# Power_driver_AMP.net
KiCad netlist of a schematic drawn in Altium Designer
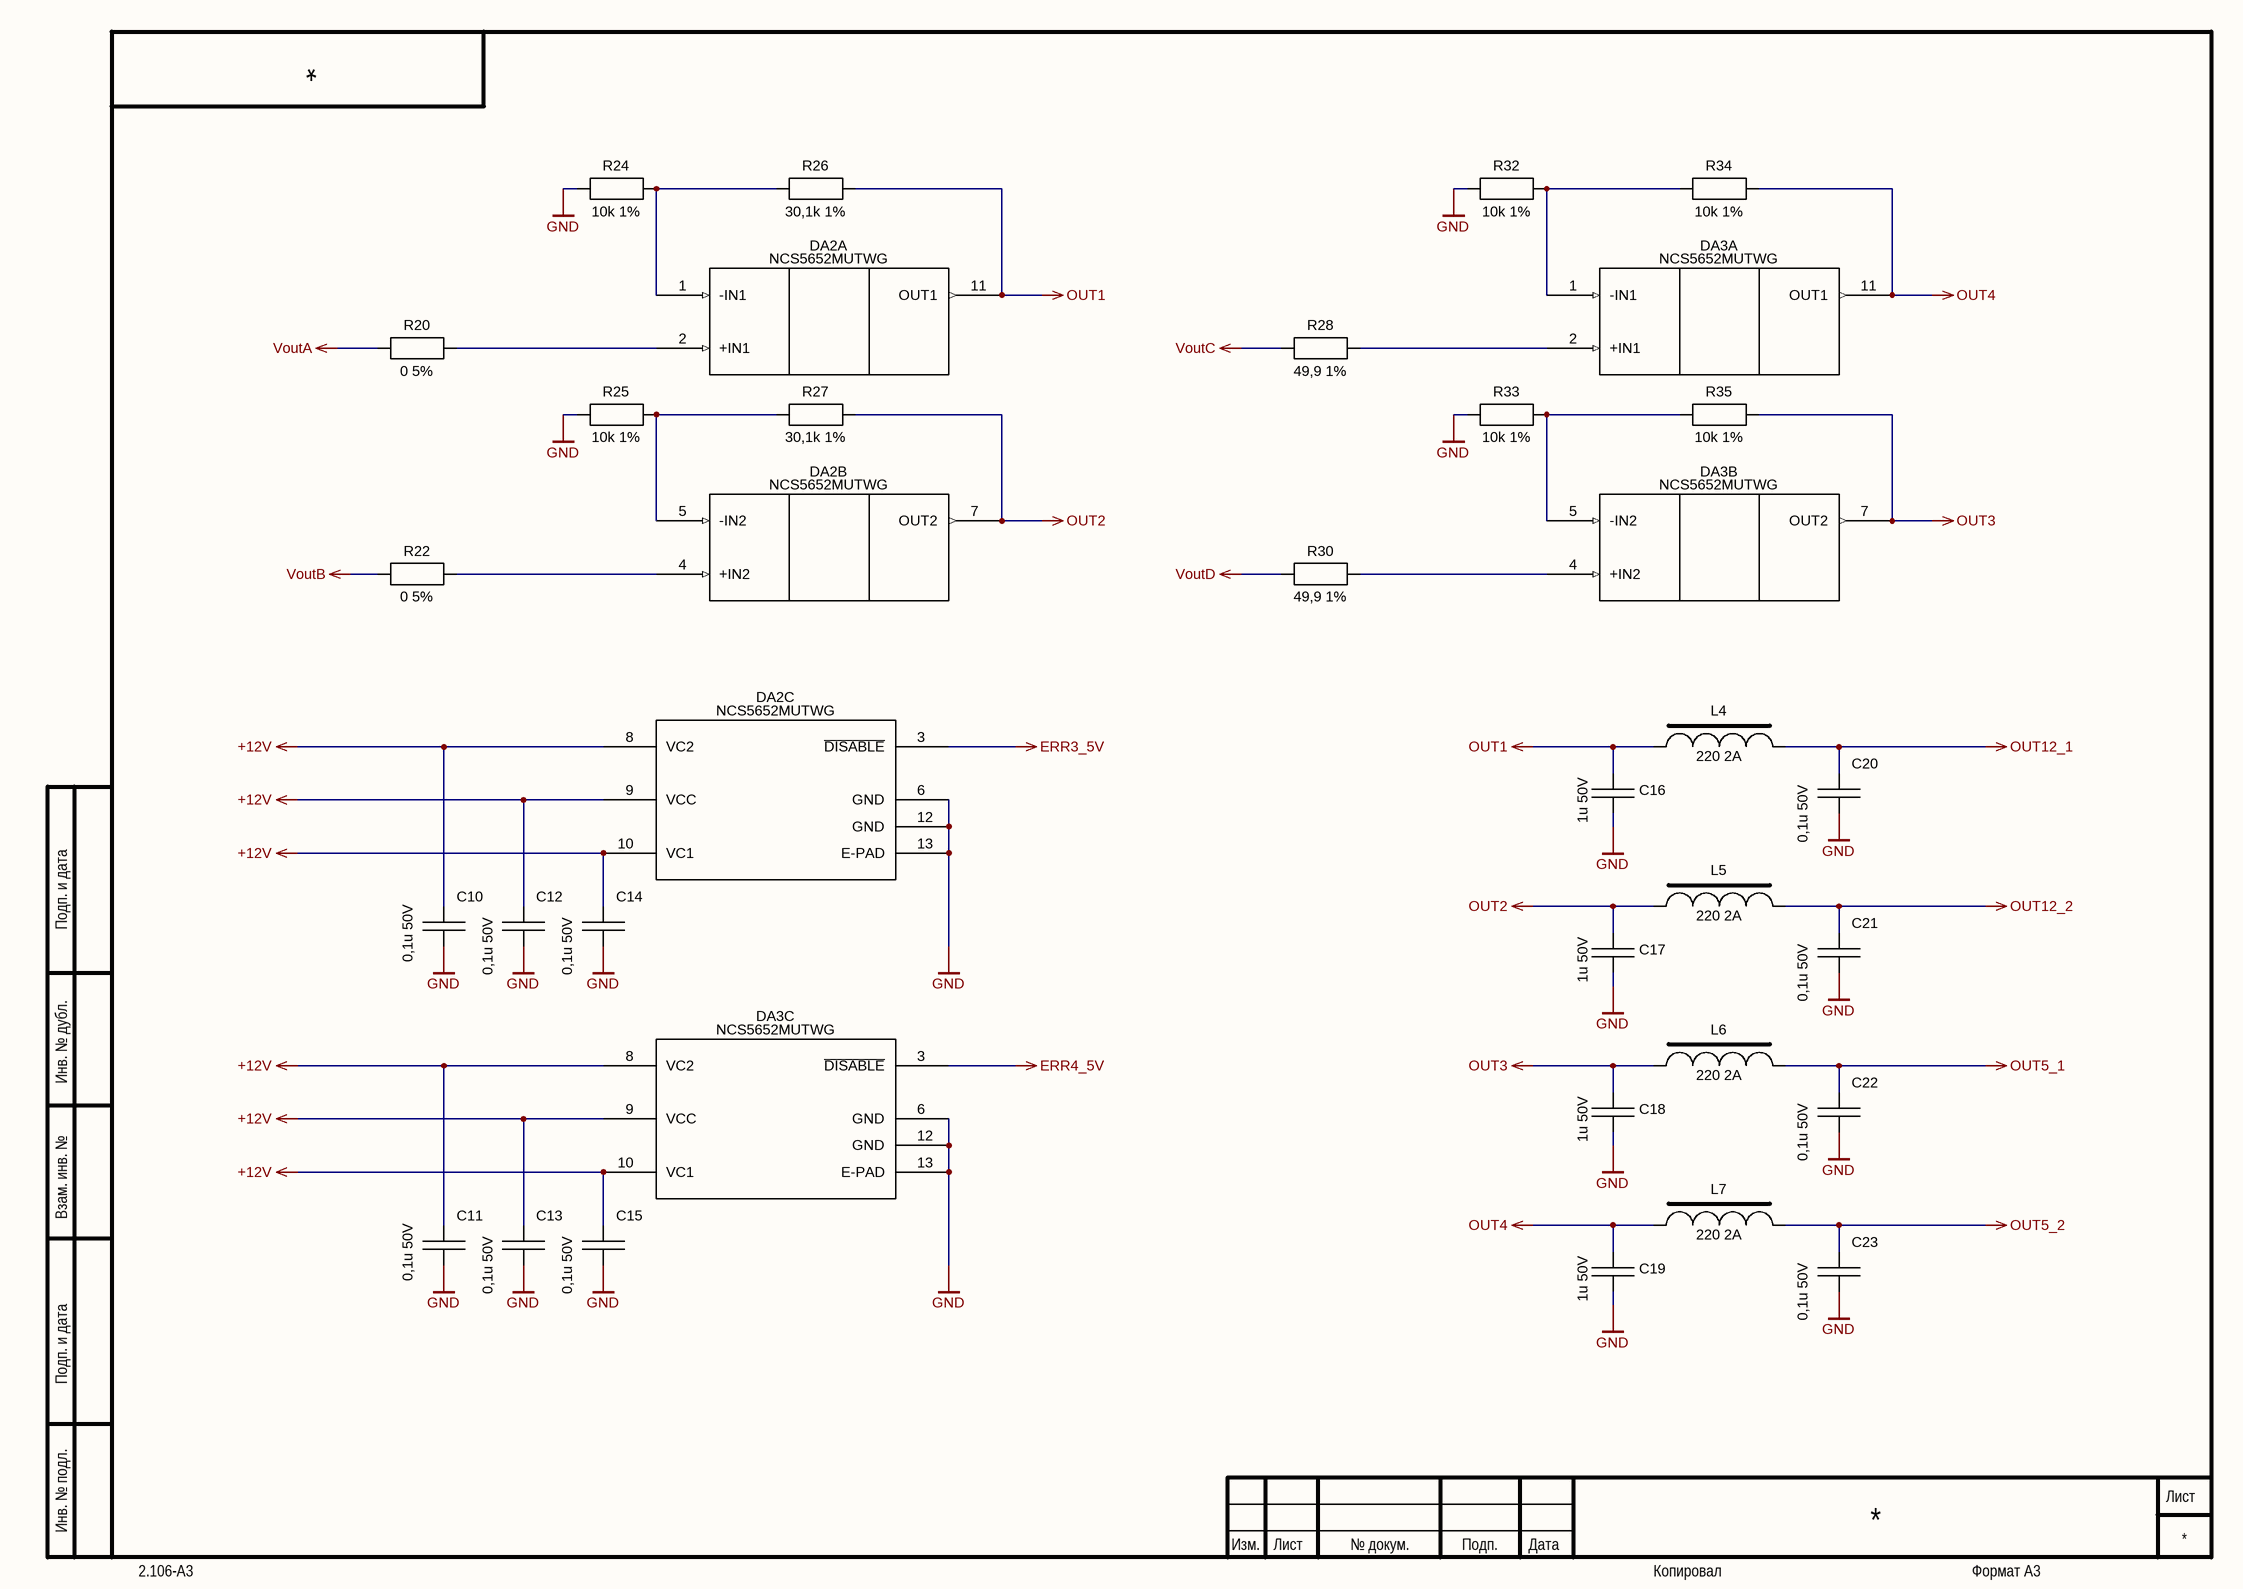
[diagram p0: Power_driver_AMP.SchDoc]

(export (version "E")
  (design (tool "Eeschema 10.0.6"))
  (components
    (comp (ref "C10")
      (value "0,1u 50V")
      (footprint "C0603_CAPC1608X09N")
      (description "Конденсатор керамический (MLCC) общего назначения 0603")
      (fields
        (field (name "PARTNUMBER") "CC0603KRX7R9BB104")
        (field (name "MANUFACTURER") "YAGEO")
        (field (name "DESIGNER") "Dudarev")
      )
      (libsource (lib "RQCLib") (part "Capacitor"))
    )
    (comp (ref "C11")
      (value "0,1u 50V")
      (footprint "C0603_CAPC1608X09N")
      (description "Конденсатор керамический (MLCC) общего назначения 0603")
      (fields
        (field (name "PARTNUMBER") "CC0603KRX7R9BB104")
        (field (name "MANUFACTURER") "YAGEO")
        (field (name "DESIGNER") "Dudarev")
      )
      (libsource (lib "RQCLib") (part "Capacitor"))
    )
    (comp (ref "C12")
      (value "0,1u 50V")
      (footprint "C0603_CAPC1608X09N")
      (description "Конденсатор керамический (MLCC) общего назначения 0603")
      (fields
        (field (name "PARTNUMBER") "CC0603KRX7R9BB104")
        (field (name "MANUFACTURER") "YAGEO")
        (field (name "DESIGNER") "Dudarev")
      )
      (libsource (lib "RQCLib") (part "Capacitor"))
    )
    (comp (ref "C13")
      (value "0,1u 50V")
      (footprint "C0603_CAPC1608X09N")
      (description "Конденсатор керамический (MLCC) общего назначения 0603")
      (fields
        (field (name "PARTNUMBER") "CC0603KRX7R9BB104")
        (field (name "MANUFACTURER") "YAGEO")
        (field (name "DESIGNER") "Dudarev")
      )
      (libsource (lib "RQCLib") (part "Capacitor"))
    )
    (comp (ref "C14")
      (value "0,1u 50V")
      (footprint "C0603_CAPC1608X09N")
      (description "Конденсатор керамический (MLCC) общего назначения 0603")
      (fields
        (field (name "PARTNUMBER") "CC0603KRX7R9BB104")
        (field (name "MANUFACTURER") "YAGEO")
        (field (name "DESIGNER") "Dudarev")
      )
      (libsource (lib "RQCLib") (part "Capacitor"))
    )
    (comp (ref "C15")
      (value "0,1u 50V")
      (footprint "C0603_CAPC1608X09N")
      (description "Конденсатор керамический (MLCC) общего назначения 0603")
      (fields
        (field (name "PARTNUMBER") "CC0603KRX7R9BB104")
        (field (name "MANUFACTURER") "YAGEO")
        (field (name "DESIGNER") "Dudarev")
      )
      (libsource (lib "RQCLib") (part "Capacitor"))
    )
    (comp (ref "C16")
      (value "1u 50V")
      (footprint "C0603_CAPC1608X09N")
      (description "Конденсатор керамический (MLCC) общего назначения 0603")
      (fields
        (field (name "PARTNUMBER") "CC0603KRX7R9BB105")
        (field (name "MANUFACTURER") "YAGEO")
        (field (name "DESIGNER") "Dudarev")
      )
      (libsource (lib "RQCLib") (part "Capacitor"))
    )
    (comp (ref "C17")
      (value "1u 50V")
      (footprint "C0603_CAPC1608X09N")
      (description "Конденсатор керамический (MLCC) общего назначения 0603")
      (fields
        (field (name "PARTNUMBER") "CC0603KRX7R9BB105")
        (field (name "MANUFACTURER") "YAGEO")
        (field (name "DESIGNER") "Dudarev")
      )
      (libsource (lib "RQCLib") (part "Capacitor"))
    )
    (comp (ref "C18")
      (value "1u 50V")
      (footprint "C0603_CAPC1608X09N")
      (description "Конденсатор керамический (MLCC) общего назначения 0603")
      (fields
        (field (name "PARTNUMBER") "CC0603KRX7R9BB105")
        (field (name "MANUFACTURER") "YAGEO")
        (field (name "DESIGNER") "Dudarev")
      )
      (libsource (lib "RQCLib") (part "Capacitor"))
    )
    (comp (ref "C19")
      (value "1u 50V")
      (footprint "C0603_CAPC1608X09N")
      (description "Конденсатор керамический (MLCC) общего назначения 0603")
      (fields
        (field (name "PARTNUMBER") "CC0603KRX7R9BB105")
        (field (name "MANUFACTURER") "YAGEO")
        (field (name "DESIGNER") "Dudarev")
      )
      (libsource (lib "RQCLib") (part "Capacitor"))
    )
    (comp (ref "C20")
      (value "0,1u 50V")
      (footprint "C0603_CAPC1608X09N")
      (description "Конденсатор керамический (MLCC) общего назначения 0603")
      (fields
        (field (name "PARTNUMBER") "CC0603KRX7R9BB104")
        (field (name "MANUFACTURER") "YAGEO")
        (field (name "DESIGNER") "Dudarev")
      )
      (libsource (lib "RQCLib") (part "Capacitor"))
    )
    (comp (ref "C21")
      (value "0,1u 50V")
      (footprint "C0603_CAPC1608X09N")
      (description "Конденсатор керамический (MLCC) общего назначения 0603")
      (fields
        (field (name "PARTNUMBER") "CC0603KRX7R9BB104")
        (field (name "MANUFACTURER") "YAGEO")
        (field (name "DESIGNER") "Dudarev")
      )
      (libsource (lib "RQCLib") (part "Capacitor"))
    )
    (comp (ref "C22")
      (value "0,1u 50V")
      (footprint "C0603_CAPC1608X09N")
      (description "Конденсатор керамический (MLCC) общего назначения 0603")
      (fields
        (field (name "PARTNUMBER") "CC0603KRX7R9BB104")
        (field (name "MANUFACTURER") "YAGEO")
        (field (name "DESIGNER") "Dudarev")
      )
      (libsource (lib "RQCLib") (part "Capacitor"))
    )
    (comp (ref "C23")
      (value "0,1u 50V")
      (footprint "C0603_CAPC1608X09N")
      (description "Конденсатор керамический (MLCC) общего назначения 0603")
      (fields
        (field (name "PARTNUMBER") "CC0603KRX7R9BB104")
        (field (name "MANUFACTURER") "YAGEO")
        (field (name "DESIGNER") "Dudarev")
      )
      (libsource (lib "RQCLib") (part "Capacitor"))
    )
    (comp (ref "DA2")
      (value "NCS5652MUTWG")
      (footprint "UDFN12 3x3, 0.5P")
      (description "High Speed, High Output Current, Dual Operational Amplifier, SMT")
      (libsource (lib "IC_Amplifier") (part "NCS5652MUTWG"))
    )
    (comp (ref "DA3")
      (value "NCS5652MUTWG")
      (footprint "UDFN12 3x3, 0.5P")
      (description "High Speed, High Output Current, Dual Operational Amplifier, SMT")
      (libsource (lib "IC_Amplifier") (part "NCS5652MUTWG"))
    )
    (comp (ref "L4")
      (value "220 2A")
      (footprint "I0805_INDC2012X11N")
      (description "Chip Ferrite Bead 220 Ohm, 2A, 0805")
      (fields
        (field (name "PARTNUMBER") "BLM21PG221SN1D")
        (field (name "MANUFACTURER") "Murata Electronics")
        (field (name "DESIGNER") "Pashinskiy")
      )
      (libsource (lib "RQCLib") (part "Inductor_Core"))
    )
    (comp (ref "L5")
      (value "220 2A")
      (footprint "I0805_INDC2012X11N")
      (description "Chip Ferrite Bead 220 Ohm, 2A, 0805")
      (fields
        (field (name "PARTNUMBER") "BLM21PG221SN1D")
        (field (name "MANUFACTURER") "Murata Electronics")
        (field (name "DESIGNER") "Pashinskiy")
      )
      (libsource (lib "RQCLib") (part "Inductor_Core"))
    )
    (comp (ref "L6")
      (value "220 2A")
      (footprint "I0805_INDC2012X11N")
      (description "Chip Ferrite Bead 220 Ohm, 2A, 0805")
      (fields
        (field (name "PARTNUMBER") "BLM21PG221SN1D")
        (field (name "MANUFACTURER") "Murata Electronics")
        (field (name "DESIGNER") "Pashinskiy")
      )
      (libsource (lib "RQCLib") (part "Inductor_Core"))
    )
    (comp (ref "L7")
      (value "220 2A")
      (footprint "I0805_INDC2012X11N")
      (description "Chip Ferrite Bead 220 Ohm, 2A, 0805")
      (fields
        (field (name "PARTNUMBER") "BLM21PG221SN1D")
        (field (name "MANUFACTURER") "Murata Electronics")
        (field (name "DESIGNER") "Pashinskiy")
      )
      (libsource (lib "RQCLib") (part "Inductor_Core"))
    )
    (comp (ref "R20")
      (value "0 5%")
      (footprint "R0603_RESC1608X06N")
      (description "Резистор толстопленочный общего назначения 0603")
      (fields
        (field (name "PARTNUMBER") "RC0603JR-070RL")
        (field (name "MANUFACTURER") "YAGEO")
        (field (name "DESIGNER") "Dudarev")
      )
      (libsource (lib "RQCLib") (part "Resistor"))
    )
    (comp (ref "R22")
      (value "0 5%")
      (footprint "R0603_RESC1608X06N")
      (description "Резистор толстопленочный общего назначения 0603")
      (fields
        (field (name "PARTNUMBER") "RC0603JR-070RL")
        (field (name "MANUFACTURER") "YAGEO")
        (field (name "DESIGNER") "Dudarev")
      )
      (libsource (lib "RQCLib") (part "Resistor"))
    )
    (comp (ref "R24")
      (value "10k 1%")
      (footprint "R0603_RESC1608X06N")
      (description "Резистор толстопленочный общего назначения 0603")
      (fields
        (field (name "PARTNUMBER") "RC0603FR-0710KL")
        (field (name "MANUFACTURER") "YAGEO")
        (field (name "DESIGNER") "Dudarev")
      )
      (libsource (lib "RQCLib") (part "Resistor"))
    )
    (comp (ref "R25")
      (value "10k 1%")
      (footprint "R0603_RESC1608X06N")
      (description "Резистор толстопленочный общего назначения 0603")
      (fields
        (field (name "PARTNUMBER") "RC0603FR-0710KL")
        (field (name "MANUFACTURER") "YAGEO")
        (field (name "DESIGNER") "Dudarev")
      )
      (libsource (lib "RQCLib") (part "Resistor"))
    )
    (comp (ref "R26")
      (value "30,1k 1%")
      (footprint "R0603_RESC1608X06N")
      (description "Резистор толстопленочный общего назначения 0603")
      (fields
        (field (name "PARTNUMBER") "RC0603FR-0730K1L")
        (field (name "MANUFACTURER") "YAGEO")
        (field (name "DESIGNER") "Dudarev")
      )
      (libsource (lib "RQCLib") (part "Resistor"))
    )
    (comp (ref "R27")
      (value "30,1k 1%")
      (footprint "R0603_RESC1608X06N")
      (description "Резистор толстопленочный общего назначения 0603")
      (fields
        (field (name "PARTNUMBER") "RC0603FR-0730K1L")
        (field (name "MANUFACTURER") "YAGEO")
        (field (name "DESIGNER") "Dudarev")
      )
      (libsource (lib "RQCLib") (part "Resistor"))
    )
    (comp (ref "R28")
      (value "49,9 1%")
      (footprint "R0603_RESC1608X06N")
      (description "Резистор толстопленочный общего назначения 0603")
      (fields
        (field (name "PARTNUMBER") "RC0603FR-0749R9L")
        (field (name "MANUFACTURER") "YAGEO")
        (field (name "DESIGNER") "Dudarev")
      )
      (libsource (lib "RQCLib") (part "Resistor"))
    )
    (comp (ref "R30")
      (value "49,9 1%")
      (footprint "R0603_RESC1608X06N")
      (description "Резистор толстопленочный общего назначения 0603")
      (fields
        (field (name "PARTNUMBER") "RC0603FR-0749R9L")
        (field (name "MANUFACTURER") "YAGEO")
        (field (name "DESIGNER") "Dudarev")
      )
      (libsource (lib "RQCLib") (part "Resistor"))
    )
    (comp (ref "R32")
      (value "10k 1%")
      (footprint "R0603_RESC1608X06N")
      (description "Резистор толстопленочный общего назначения 0603")
      (fields
        (field (name "PARTNUMBER") "RC0603FR-0710KL")
        (field (name "MANUFACTURER") "YAGEO")
        (field (name "DESIGNER") "Dudarev")
      )
      (libsource (lib "RQCLib") (part "Resistor"))
    )
    (comp (ref "R33")
      (value "10k 1%")
      (footprint "R0603_RESC1608X06N")
      (description "Резистор толстопленочный общего назначения 0603")
      (fields
        (field (name "PARTNUMBER") "RC0603FR-0710KL")
        (field (name "MANUFACTURER") "YAGEO")
        (field (name "DESIGNER") "Dudarev")
      )
      (libsource (lib "RQCLib") (part "Resistor"))
    )
    (comp (ref "R34")
      (value "10k 1%")
      (footprint "R0603_RESC1608X06N")
      (description "Резистор толстопленочный общего назначения 0603")
      (fields
        (field (name "PARTNUMBER") "RC0603FR-0710KL")
        (field (name "MANUFACTURER") "YAGEO")
        (field (name "DESIGNER") "Dudarev")
      )
      (libsource (lib "RQCLib") (part "Resistor"))
    )
    (comp (ref "R35")
      (value "10k 1%")
      (footprint "R0603_RESC1608X06N")
      (description "Резистор толстопленочный общего назначения 0603")
      (fields
        (field (name "PARTNUMBER") "RC0603FR-0710KL")
        (field (name "MANUFACTURER") "YAGEO")
        (field (name "DESIGNER") "Dudarev")
      )
      (libsource (lib "RQCLib") (part "Resistor"))
    )
  )
  (nets
    (net (code "1") (name "+12V") (class "Default")
      (node (ref "C10") (pin "1") (pinfunction "1_1") (pintype "passive"))
      (node (ref "C11") (pin "1") (pinfunction "1_1") (pintype "passive"))
      (node (ref "C12") (pin "1") (pinfunction "1_1") (pintype "passive"))
      (node (ref "C13") (pin "1") (pinfunction "1_1") (pintype "passive"))
      (node (ref "C14") (pin "1") (pinfunction "1_1") (pintype "passive"))
      (node (ref "C15") (pin "1") (pinfunction "1_1") (pintype "passive"))
      (node (ref "DA2") (pin "10") (pinfunction "VC1_10") (pintype "power_in"))
      (node (ref "DA2") (pin "8") (pinfunction "VC2_8") (pintype "power_in"))
      (node (ref "DA2") (pin "9") (pinfunction "VCC_9") (pintype "power_in"))
      (node (ref "DA3") (pin "10") (pinfunction "VC1_10") (pintype "power_in"))
      (node (ref "DA3") (pin "8") (pinfunction "VC2_8") (pintype "power_in"))
      (node (ref "DA3") (pin "9") (pinfunction "VCC_9") (pintype "power_in"))
    )
    (net (code "2") (name "ERR3_5V") (class "Default")
      (node (ref "DA2") (pin "3") (pinfunction "~{DISABLE}_3") (pintype "power_in"))
    )
    (net (code "3") (name "ERR4_5V") (class "Default")
      (node (ref "DA3") (pin "3") (pinfunction "~{DISABLE}_3") (pintype "power_in"))
    )
    (net (code "4") (name "GND") (class "Default")
      (node (ref "C10") (pin "2") (pinfunction "2_2") (pintype "passive"))
      (node (ref "C11") (pin "2") (pinfunction "2_2") (pintype "passive"))
      (node (ref "C12") (pin "2") (pinfunction "2_2") (pintype "passive"))
      (node (ref "C13") (pin "2") (pinfunction "2_2") (pintype "passive"))
      (node (ref "C14") (pin "2") (pinfunction "2_2") (pintype "passive"))
      (node (ref "C15") (pin "2") (pinfunction "2_2") (pintype "passive"))
      (node (ref "C16") (pin "1") (pinfunction "1_1") (pintype "passive"))
      (node (ref "C17") (pin "1") (pinfunction "1_1") (pintype "passive"))
      (node (ref "C18") (pin "1") (pinfunction "1_1") (pintype "passive"))
      (node (ref "C19") (pin "1") (pinfunction "1_1") (pintype "passive"))
      (node (ref "C20") (pin "2") (pinfunction "2_2") (pintype "passive"))
      (node (ref "C21") (pin "2") (pinfunction "2_2") (pintype "passive"))
      (node (ref "C22") (pin "2") (pinfunction "2_2") (pintype "passive"))
      (node (ref "C23") (pin "2") (pinfunction "2_2") (pintype "passive"))
      (node (ref "DA2") (pin "12") (pinfunction "GND_12") (pintype "power_in"))
      (node (ref "DA2") (pin "13") (pinfunction "E-PAD_13") (pintype "power_in"))
      (node (ref "DA2") (pin "6") (pinfunction "GND_6") (pintype "power_in"))
      (node (ref "DA3") (pin "12") (pinfunction "GND_12") (pintype "power_in"))
      (node (ref "DA3") (pin "13") (pinfunction "E-PAD_13") (pintype "power_in"))
      (node (ref "DA3") (pin "6") (pinfunction "GND_6") (pintype "power_in"))
      (node (ref "R24") (pin "1") (pinfunction "1_1") (pintype "passive"))
      (node (ref "R25") (pin "1") (pinfunction "1_1") (pintype "passive"))
      (node (ref "R32") (pin "1") (pinfunction "1_1") (pintype "passive"))
      (node (ref "R33") (pin "1") (pinfunction "1_1") (pintype "passive"))
    )
    (net (code "5") (name "Net-(DA2A-+IN1)") (class "Default")
      (node (ref "DA2") (pin "2") (pinfunction "+IN1_2") (pintype "input"))
      (node (ref "R20") (pin "2") (pinfunction "2_2") (pintype "passive"))
    )
    (net (code "6") (name "Net-(DA2A--IN1)") (class "Default")
      (node (ref "DA2") (pin "1") (pinfunction "-IN1_1") (pintype "input"))
      (node (ref "R24") (pin "2") (pinfunction "2_2") (pintype "passive"))
      (node (ref "R26") (pin "1") (pinfunction "1_1") (pintype "passive"))
    )
    (net (code "7") (name "Net-(DA2B-+IN2)") (class "Default")
      (node (ref "DA2") (pin "4") (pinfunction "+IN2_4") (pintype "input"))
      (node (ref "R22") (pin "2") (pinfunction "2_2") (pintype "passive"))
    )
    (net (code "8") (name "Net-(DA2B--IN2)") (class "Default")
      (node (ref "DA2") (pin "5") (pinfunction "-IN2_5") (pintype "input"))
      (node (ref "R25") (pin "2") (pinfunction "2_2") (pintype "passive"))
      (node (ref "R27") (pin "1") (pinfunction "1_1") (pintype "passive"))
    )
    (net (code "9") (name "Net-(DA3A-+IN1)") (class "Default")
      (node (ref "DA3") (pin "2") (pinfunction "+IN1_2") (pintype "input"))
      (node (ref "R28") (pin "2") (pinfunction "2_2") (pintype "passive"))
    )
    (net (code "10") (name "Net-(DA3A--IN1)") (class "Default")
      (node (ref "DA3") (pin "1") (pinfunction "-IN1_1") (pintype "input"))
      (node (ref "R32") (pin "2") (pinfunction "2_2") (pintype "passive"))
      (node (ref "R34") (pin "1") (pinfunction "1_1") (pintype "passive"))
    )
    (net (code "11") (name "Net-(DA3B-+IN2)") (class "Default")
      (node (ref "DA3") (pin "4") (pinfunction "+IN2_4") (pintype "input"))
      (node (ref "R30") (pin "2") (pinfunction "2_2") (pintype "passive"))
    )
    (net (code "12") (name "Net-(DA3B--IN2)") (class "Default")
      (node (ref "DA3") (pin "5") (pinfunction "-IN2_5") (pintype "input"))
      (node (ref "R33") (pin "2") (pinfunction "2_2") (pintype "passive"))
      (node (ref "R35") (pin "1") (pinfunction "1_1") (pintype "passive"))
    )
    (net (code "13") (name "OUT1") (class "Default")
      (node (ref "C16") (pin "2") (pinfunction "2_2") (pintype "passive"))
      (node (ref "DA2") (pin "11") (pinfunction "OUT1_11") (pintype "output"))
      (node (ref "L4") (pin "1") (pinfunction "1_1") (pintype "passive"))
      (node (ref "R26") (pin "2") (pinfunction "2_2") (pintype "passive"))
    )
    (net (code "14") (name "OUT2") (class "Default")
      (node (ref "C17") (pin "2") (pinfunction "2_2") (pintype "passive"))
      (node (ref "DA2") (pin "7") (pinfunction "OUT2_7") (pintype "output"))
      (node (ref "L5") (pin "1") (pinfunction "1_1") (pintype "passive"))
      (node (ref "R27") (pin "2") (pinfunction "2_2") (pintype "passive"))
    )
    (net (code "15") (name "OUT3") (class "Default")
      (node (ref "C18") (pin "2") (pinfunction "2_2") (pintype "passive"))
      (node (ref "DA3") (pin "7") (pinfunction "OUT2_7") (pintype "output"))
      (node (ref "L6") (pin "1") (pinfunction "1_1") (pintype "passive"))
      (node (ref "R35") (pin "2") (pinfunction "2_2") (pintype "passive"))
    )
    (net (code "16") (name "OUT4") (class "Default")
      (node (ref "C19") (pin "2") (pinfunction "2_2") (pintype "passive"))
      (node (ref "DA3") (pin "11") (pinfunction "OUT1_11") (pintype "output"))
      (node (ref "L7") (pin "1") (pinfunction "1_1") (pintype "passive"))
      (node (ref "R34") (pin "2") (pinfunction "2_2") (pintype "passive"))
    )
    (net (code "17") (name "OUT5_1") (class "Default")
      (node (ref "C22") (pin "1") (pinfunction "1_1") (pintype "passive"))
      (node (ref "L6") (pin "2") (pinfunction "2_2") (pintype "passive"))
    )
    (net (code "18") (name "OUT5_2") (class "Default")
      (node (ref "C23") (pin "1") (pinfunction "1_1") (pintype "passive"))
      (node (ref "L7") (pin "2") (pinfunction "2_2") (pintype "passive"))
    )
    (net (code "19") (name "OUT12_1") (class "Default")
      (node (ref "C20") (pin "1") (pinfunction "1_1") (pintype "passive"))
      (node (ref "L4") (pin "2") (pinfunction "2_2") (pintype "passive"))
    )
    (net (code "20") (name "OUT12_2") (class "Default")
      (node (ref "C21") (pin "1") (pinfunction "1_1") (pintype "passive"))
      (node (ref "L5") (pin "2") (pinfunction "2_2") (pintype "passive"))
    )
    (net (code "21") (name "VoutA") (class "Default")
      (node (ref "R20") (pin "1") (pinfunction "1_1") (pintype "passive"))
    )
    (net (code "22") (name "VoutB") (class "Default")
      (node (ref "R22") (pin "1") (pinfunction "1_1") (pintype "passive"))
    )
    (net (code "23") (name "VoutC") (class "Default")
      (node (ref "R28") (pin "1") (pinfunction "1_1") (pintype "passive"))
    )
    (net (code "24") (name "VoutD") (class "Default")
      (node (ref "R30") (pin "1") (pinfunction "1_1") (pintype "passive"))
    )
  )
)
